# Sheet3.net
KiCad netlist of a schematic drawn in Altium Designer
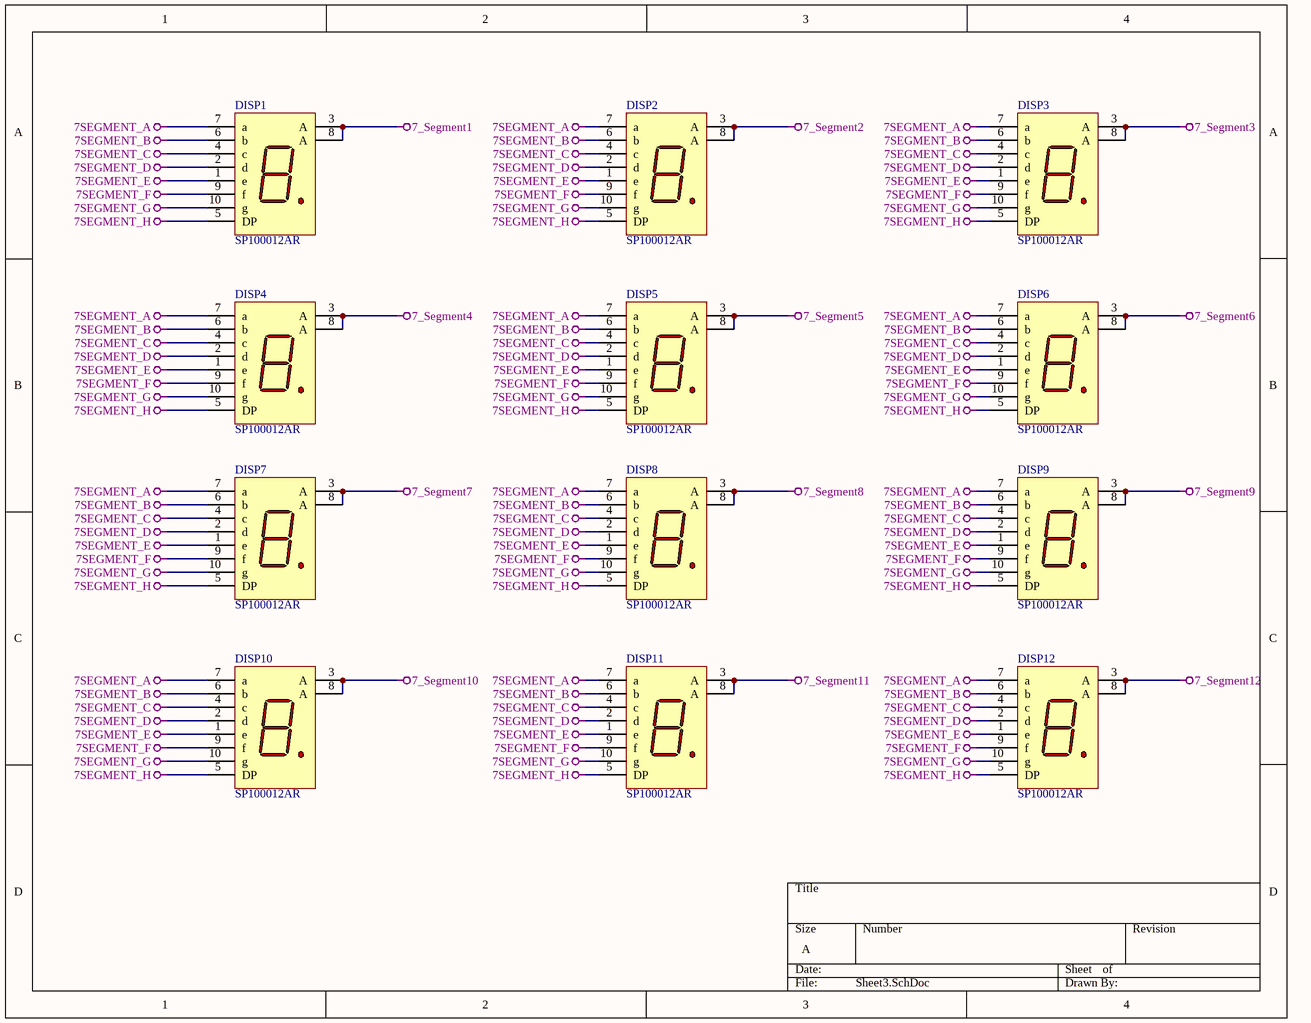
[diagram p0: Sheet3.SchDoc]

(export (version "E")
  (design (tool "Eeschema 10.0.6"))
  (components
    (comp (ref "DISP1")
      (value "SP100012AR")
      (footprint "SP10012AR-HILIGHT")
      (description "34mm/1200mil")
      (libsource (lib "VIJAYIntegrated_Library") (part "SP100012AR"))
    )
    (comp (ref "DISP2")
      (value "SP100012AR")
      (footprint "SP10012AR-HILIGHT")
      (description "34mm/1200mil")
      (libsource (lib "VIJAYIntegrated_Library") (part "SP100012AR"))
    )
    (comp (ref "DISP3")
      (value "SP100012AR")
      (footprint "SP10012AR-HILIGHT")
      (description "34mm/1200mil")
      (libsource (lib "VIJAYIntegrated_Library") (part "SP100012AR"))
    )
    (comp (ref "DISP4")
      (value "SP100012AR")
      (footprint "SP10012AR-HILIGHT")
      (description "34mm/1200mil")
      (libsource (lib "VIJAYIntegrated_Library") (part "SP100012AR"))
    )
    (comp (ref "DISP5")
      (value "SP100012AR")
      (footprint "SP10012AR-HILIGHT")
      (description "34mm/1200mil")
      (libsource (lib "VIJAYIntegrated_Library") (part "SP100012AR"))
    )
    (comp (ref "DISP6")
      (value "SP100012AR")
      (footprint "SP10012AR-HILIGHT")
      (description "34mm/1200mil")
      (libsource (lib "VIJAYIntegrated_Library") (part "SP100012AR"))
    )
    (comp (ref "DISP7")
      (value "SP100012AR")
      (footprint "SP10012AR-HILIGHT")
      (description "34mm/1200mil")
      (libsource (lib "VIJAYIntegrated_Library") (part "SP100012AR"))
    )
    (comp (ref "DISP8")
      (value "SP100012AR")
      (footprint "SP10012AR-HILIGHT")
      (description "34mm/1200mil")
      (libsource (lib "VIJAYIntegrated_Library") (part "SP100012AR"))
    )
    (comp (ref "DISP9")
      (value "SP100012AR")
      (footprint "SP10012AR-HILIGHT")
      (description "34mm/1200mil")
      (libsource (lib "VIJAYIntegrated_Library") (part "SP100012AR"))
    )
    (comp (ref "DISP10")
      (value "SP100012AR")
      (footprint "SP10012AR-HILIGHT")
      (description "34mm/1200mil")
      (libsource (lib "VIJAYIntegrated_Library") (part "SP100012AR"))
    )
    (comp (ref "DISP11")
      (value "SP100012AR")
      (footprint "SP10012AR-HILIGHT")
      (description "34mm/1200mil")
      (libsource (lib "VIJAYIntegrated_Library") (part "SP100012AR"))
    )
    (comp (ref "DISP12")
      (value "SP100012AR")
      (footprint "SP10012AR-HILIGHT")
      (description "34mm/1200mil")
      (libsource (lib "VIJAYIntegrated_Library") (part "SP100012AR"))
    )
  )
  (nets
    (net (code "1") (name "7SEGMENT_A") (class "Default")
      (node (ref "DISP1") (pin "7") (pinfunction "a_7") (pintype "passive"))
      (node (ref "DISP10") (pin "7") (pinfunction "a_7") (pintype "passive"))
      (node (ref "DISP11") (pin "7") (pinfunction "a_7") (pintype "passive"))
      (node (ref "DISP12") (pin "7") (pinfunction "a_7") (pintype "passive"))
      (node (ref "DISP2") (pin "7") (pinfunction "a_7") (pintype "passive"))
      (node (ref "DISP3") (pin "7") (pinfunction "a_7") (pintype "passive"))
      (node (ref "DISP4") (pin "7") (pinfunction "a_7") (pintype "passive"))
      (node (ref "DISP5") (pin "7") (pinfunction "a_7") (pintype "passive"))
      (node (ref "DISP6") (pin "7") (pinfunction "a_7") (pintype "passive"))
      (node (ref "DISP7") (pin "7") (pinfunction "a_7") (pintype "passive"))
      (node (ref "DISP8") (pin "7") (pinfunction "a_7") (pintype "passive"))
      (node (ref "DISP9") (pin "7") (pinfunction "a_7") (pintype "passive"))
    )
    (net (code "2") (name "7SEGMENT_B") (class "Default")
      (node (ref "DISP1") (pin "6") (pinfunction "b_6") (pintype "passive"))
      (node (ref "DISP10") (pin "6") (pinfunction "b_6") (pintype "passive"))
      (node (ref "DISP11") (pin "6") (pinfunction "b_6") (pintype "passive"))
      (node (ref "DISP12") (pin "6") (pinfunction "b_6") (pintype "passive"))
      (node (ref "DISP2") (pin "6") (pinfunction "b_6") (pintype "passive"))
      (node (ref "DISP3") (pin "6") (pinfunction "b_6") (pintype "passive"))
      (node (ref "DISP4") (pin "6") (pinfunction "b_6") (pintype "passive"))
      (node (ref "DISP5") (pin "6") (pinfunction "b_6") (pintype "passive"))
      (node (ref "DISP6") (pin "6") (pinfunction "b_6") (pintype "passive"))
      (node (ref "DISP7") (pin "6") (pinfunction "b_6") (pintype "passive"))
      (node (ref "DISP8") (pin "6") (pinfunction "b_6") (pintype "passive"))
      (node (ref "DISP9") (pin "6") (pinfunction "b_6") (pintype "passive"))
    )
    (net (code "3") (name "7SEGMENT_C") (class "Default")
      (node (ref "DISP1") (pin "4") (pinfunction "c_4") (pintype "passive"))
      (node (ref "DISP10") (pin "4") (pinfunction "c_4") (pintype "passive"))
      (node (ref "DISP11") (pin "4") (pinfunction "c_4") (pintype "passive"))
      (node (ref "DISP12") (pin "4") (pinfunction "c_4") (pintype "passive"))
      (node (ref "DISP2") (pin "4") (pinfunction "c_4") (pintype "passive"))
      (node (ref "DISP3") (pin "4") (pinfunction "c_4") (pintype "passive"))
      (node (ref "DISP4") (pin "4") (pinfunction "c_4") (pintype "passive"))
      (node (ref "DISP5") (pin "4") (pinfunction "c_4") (pintype "passive"))
      (node (ref "DISP6") (pin "4") (pinfunction "c_4") (pintype "passive"))
      (node (ref "DISP7") (pin "4") (pinfunction "c_4") (pintype "passive"))
      (node (ref "DISP8") (pin "4") (pinfunction "c_4") (pintype "passive"))
      (node (ref "DISP9") (pin "4") (pinfunction "c_4") (pintype "passive"))
    )
    (net (code "4") (name "7SEGMENT_D") (class "Default")
      (node (ref "DISP1") (pin "2") (pinfunction "d_2") (pintype "passive"))
      (node (ref "DISP10") (pin "2") (pinfunction "d_2") (pintype "passive"))
      (node (ref "DISP11") (pin "2") (pinfunction "d_2") (pintype "passive"))
      (node (ref "DISP12") (pin "2") (pinfunction "d_2") (pintype "passive"))
      (node (ref "DISP2") (pin "2") (pinfunction "d_2") (pintype "passive"))
      (node (ref "DISP3") (pin "2") (pinfunction "d_2") (pintype "passive"))
      (node (ref "DISP4") (pin "2") (pinfunction "d_2") (pintype "passive"))
      (node (ref "DISP5") (pin "2") (pinfunction "d_2") (pintype "passive"))
      (node (ref "DISP6") (pin "2") (pinfunction "d_2") (pintype "passive"))
      (node (ref "DISP7") (pin "2") (pinfunction "d_2") (pintype "passive"))
      (node (ref "DISP8") (pin "2") (pinfunction "d_2") (pintype "passive"))
      (node (ref "DISP9") (pin "2") (pinfunction "d_2") (pintype "passive"))
    )
    (net (code "5") (name "7SEGMENT_E") (class "Default")
      (node (ref "DISP1") (pin "1") (pinfunction "e_1") (pintype "passive"))
      (node (ref "DISP10") (pin "1") (pinfunction "e_1") (pintype "passive"))
      (node (ref "DISP11") (pin "1") (pinfunction "e_1") (pintype "passive"))
      (node (ref "DISP12") (pin "1") (pinfunction "e_1") (pintype "passive"))
      (node (ref "DISP2") (pin "1") (pinfunction "e_1") (pintype "passive"))
      (node (ref "DISP3") (pin "1") (pinfunction "e_1") (pintype "passive"))
      (node (ref "DISP4") (pin "1") (pinfunction "e_1") (pintype "passive"))
      (node (ref "DISP5") (pin "1") (pinfunction "e_1") (pintype "passive"))
      (node (ref "DISP6") (pin "1") (pinfunction "e_1") (pintype "passive"))
      (node (ref "DISP7") (pin "1") (pinfunction "e_1") (pintype "passive"))
      (node (ref "DISP8") (pin "1") (pinfunction "e_1") (pintype "passive"))
      (node (ref "DISP9") (pin "1") (pinfunction "e_1") (pintype "passive"))
    )
    (net (code "6") (name "7SEGMENT_F") (class "Default")
      (node (ref "DISP1") (pin "9") (pinfunction "f_9") (pintype "passive"))
      (node (ref "DISP10") (pin "9") (pinfunction "f_9") (pintype "passive"))
      (node (ref "DISP11") (pin "9") (pinfunction "f_9") (pintype "passive"))
      (node (ref "DISP12") (pin "9") (pinfunction "f_9") (pintype "passive"))
      (node (ref "DISP2") (pin "9") (pinfunction "f_9") (pintype "passive"))
      (node (ref "DISP3") (pin "9") (pinfunction "f_9") (pintype "passive"))
      (node (ref "DISP4") (pin "9") (pinfunction "f_9") (pintype "passive"))
      (node (ref "DISP5") (pin "9") (pinfunction "f_9") (pintype "passive"))
      (node (ref "DISP6") (pin "9") (pinfunction "f_9") (pintype "passive"))
      (node (ref "DISP7") (pin "9") (pinfunction "f_9") (pintype "passive"))
      (node (ref "DISP8") (pin "9") (pinfunction "f_9") (pintype "passive"))
      (node (ref "DISP9") (pin "9") (pinfunction "f_9") (pintype "passive"))
    )
    (net (code "7") (name "7SEGMENT_G") (class "Default")
      (node (ref "DISP1") (pin "10") (pinfunction "g_10") (pintype "passive"))
      (node (ref "DISP10") (pin "10") (pinfunction "g_10") (pintype "passive"))
      (node (ref "DISP11") (pin "10") (pinfunction "g_10") (pintype "passive"))
      (node (ref "DISP12") (pin "10") (pinfunction "g_10") (pintype "passive"))
      (node (ref "DISP2") (pin "10") (pinfunction "g_10") (pintype "passive"))
      (node (ref "DISP3") (pin "10") (pinfunction "g_10") (pintype "passive"))
      (node (ref "DISP4") (pin "10") (pinfunction "g_10") (pintype "passive"))
      (node (ref "DISP5") (pin "10") (pinfunction "g_10") (pintype "passive"))
      (node (ref "DISP6") (pin "10") (pinfunction "g_10") (pintype "passive"))
      (node (ref "DISP7") (pin "10") (pinfunction "g_10") (pintype "passive"))
      (node (ref "DISP8") (pin "10") (pinfunction "g_10") (pintype "passive"))
      (node (ref "DISP9") (pin "10") (pinfunction "g_10") (pintype "passive"))
    )
    (net (code "8") (name "7SEGMENT_H") (class "Default")
      (node (ref "DISP1") (pin "5") (pinfunction "DP_5") (pintype "passive"))
      (node (ref "DISP10") (pin "5") (pinfunction "DP_5") (pintype "passive"))
      (node (ref "DISP11") (pin "5") (pinfunction "DP_5") (pintype "passive"))
      (node (ref "DISP12") (pin "5") (pinfunction "DP_5") (pintype "passive"))
      (node (ref "DISP2") (pin "5") (pinfunction "DP_5") (pintype "passive"))
      (node (ref "DISP3") (pin "5") (pinfunction "DP_5") (pintype "passive"))
      (node (ref "DISP4") (pin "5") (pinfunction "DP_5") (pintype "passive"))
      (node (ref "DISP5") (pin "5") (pinfunction "DP_5") (pintype "passive"))
      (node (ref "DISP6") (pin "5") (pinfunction "DP_5") (pintype "passive"))
      (node (ref "DISP7") (pin "5") (pinfunction "DP_5") (pintype "passive"))
      (node (ref "DISP8") (pin "5") (pinfunction "DP_5") (pintype "passive"))
      (node (ref "DISP9") (pin "5") (pinfunction "DP_5") (pintype "passive"))
    )
    (net (code "9") (name "7_Segment1") (class "Default")
      (node (ref "DISP1") (pin "3") (pinfunction "A_3") (pintype "passive"))
      (node (ref "DISP1") (pin "8") (pinfunction "A_8") (pintype "passive"))
    )
    (net (code "10") (name "7_Segment2") (class "Default")
      (node (ref "DISP2") (pin "3") (pinfunction "A_3") (pintype "passive"))
      (node (ref "DISP2") (pin "8") (pinfunction "A_8") (pintype "passive"))
    )
    (net (code "11") (name "7_Segment3") (class "Default")
      (node (ref "DISP3") (pin "3") (pinfunction "A_3") (pintype "passive"))
      (node (ref "DISP3") (pin "8") (pinfunction "A_8") (pintype "passive"))
    )
    (net (code "12") (name "7_Segment4") (class "Default")
      (node (ref "DISP4") (pin "3") (pinfunction "A_3") (pintype "passive"))
      (node (ref "DISP4") (pin "8") (pinfunction "A_8") (pintype "passive"))
    )
    (net (code "13") (name "7_Segment5") (class "Default")
      (node (ref "DISP5") (pin "3") (pinfunction "A_3") (pintype "passive"))
      (node (ref "DISP5") (pin "8") (pinfunction "A_8") (pintype "passive"))
    )
    (net (code "14") (name "7_Segment6") (class "Default")
      (node (ref "DISP6") (pin "3") (pinfunction "A_3") (pintype "passive"))
      (node (ref "DISP6") (pin "8") (pinfunction "A_8") (pintype "passive"))
    )
    (net (code "15") (name "7_Segment7") (class "Default")
      (node (ref "DISP7") (pin "3") (pinfunction "A_3") (pintype "passive"))
      (node (ref "DISP7") (pin "8") (pinfunction "A_8") (pintype "passive"))
    )
    (net (code "16") (name "7_Segment8") (class "Default")
      (node (ref "DISP8") (pin "3") (pinfunction "A_3") (pintype "passive"))
      (node (ref "DISP8") (pin "8") (pinfunction "A_8") (pintype "passive"))
    )
    (net (code "17") (name "7_Segment9") (class "Default")
      (node (ref "DISP9") (pin "3") (pinfunction "A_3") (pintype "passive"))
      (node (ref "DISP9") (pin "8") (pinfunction "A_8") (pintype "passive"))
    )
    (net (code "18") (name "7_Segment10") (class "Default")
      (node (ref "DISP10") (pin "3") (pinfunction "A_3") (pintype "passive"))
      (node (ref "DISP10") (pin "8") (pinfunction "A_8") (pintype "passive"))
    )
    (net (code "19") (name "7_Segment11") (class "Default")
      (node (ref "DISP11") (pin "3") (pinfunction "A_3") (pintype "passive"))
      (node (ref "DISP11") (pin "8") (pinfunction "A_8") (pintype "passive"))
    )
    (net (code "20") (name "7_Segment12") (class "Default")
      (node (ref "DISP12") (pin "3") (pinfunction "A_3") (pintype "passive"))
      (node (ref "DISP12") (pin "8") (pinfunction "A_8") (pintype "passive"))
    )
  )
)
